# TM4C123GH6PMI.net
KiCad netlist of a schematic drawn in Altium Designer
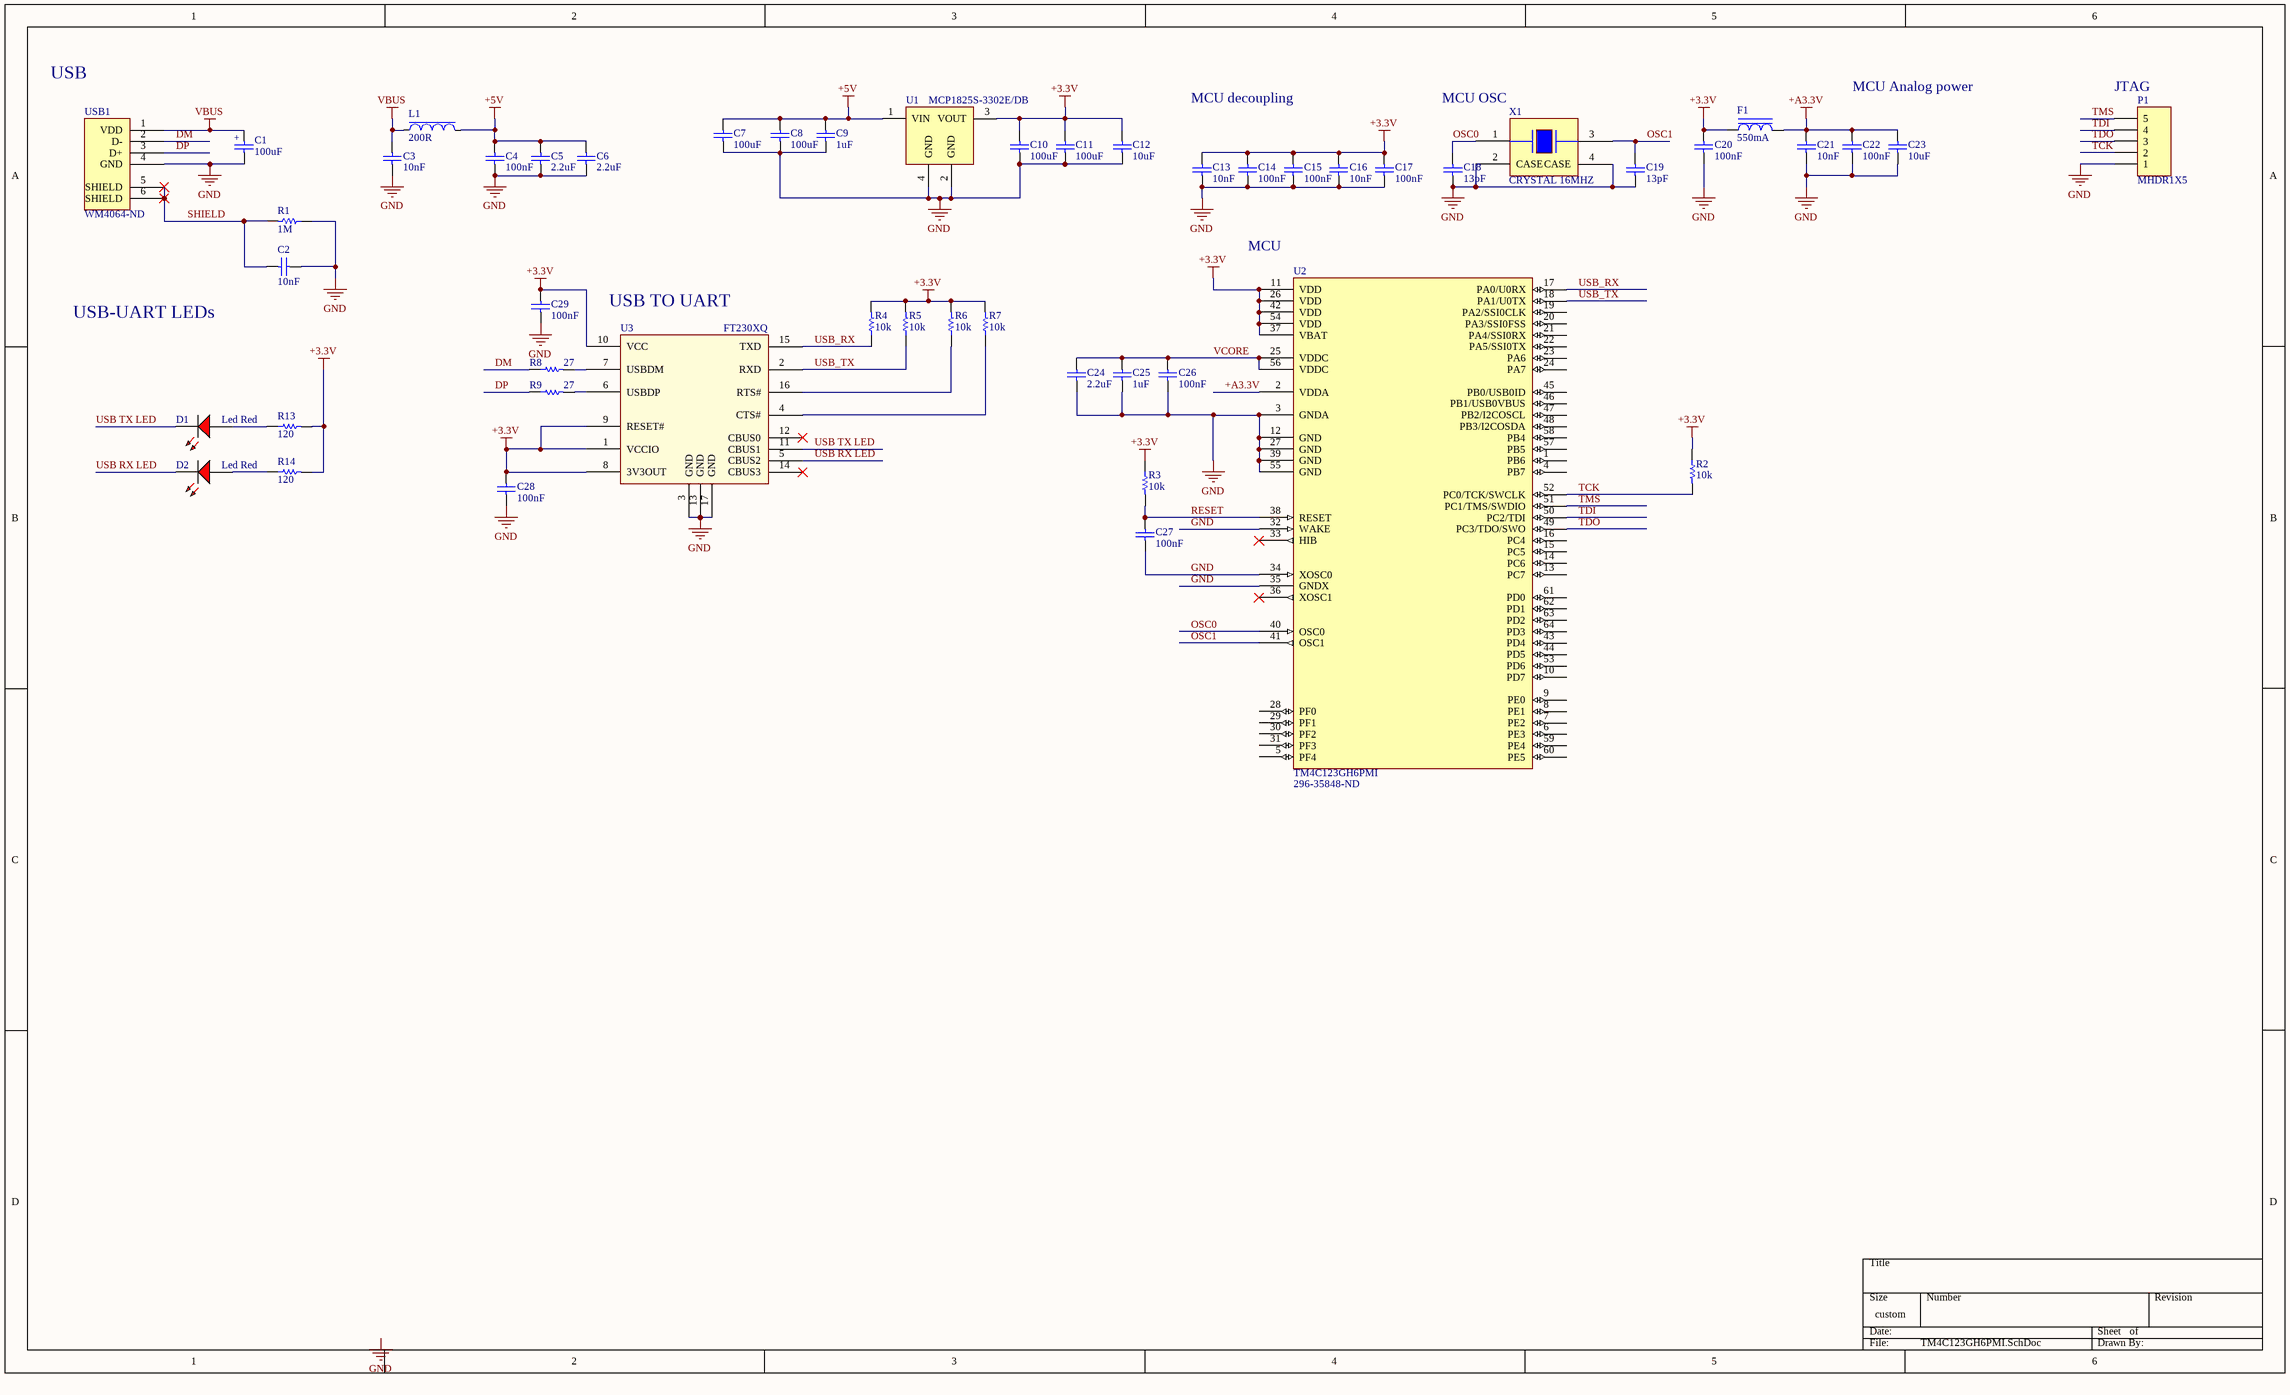
[diagram p0: TM4C123GH6PMI.SchDoc]

(export (version "E")
  (design (tool "Eeschema 10.0.6"))
  (components
    (comp (ref "C1")
      (value "100uF")
      (footprint "CapAlu6.3mmx12.5mm")
      (description "Capacitor 35v 100uF 6.3mm")
      (fields
        (field (name "MANUFACTURER") "Nichicon")
        (field (name "MANUFACTURER PART NUMBER") "UHV1V101MED")
      )
      (libsource (lib "Capacitors") (part "100uF_35v_6.3x12.5"))
    )
    (comp (ref "C2")
      (value "10nF")
      (footprint "CAP_1206")
      (description "CAP CER 10000PF 500V X7R 1206")
      (fields
        (field (name "MANUFACTURER") "Samsung Electro-Mechanics America, Inc")
        (field (name "MANUFACTURER PART NUMBER") "CL31B103KGFNNNE")
      )
      (libsource (lib "Capacitors") (part "10nF_500V_1206"))
    )
    (comp (ref "C3")
      (value "10nF")
      (footprint "CAP_0402_M")
      (description "CAP CER 10000PF 50V 10% X7R 0402")
      (fields
        (field (name "MANUFACTURER") "Kemet")
        (field (name "MANUFACTURER PART NUMBER") "C0402C103K5RACTU")
      )
      (libsource (lib "Capacitors") (part "10nF_50V_0402"))
    )
    (comp (ref "C4")
      (value "100nF")
      (footprint "CAP_0402_M")
      (description "CAP CER 100NF 50V 20% X5R 0402")
      (fields
        (field (name "MANUFACTURER") "TDK Corporation")
        (field (name "MANUFACTURER PART NUMBER") "C1005X5R1H104M050BB")
      )
      (libsource (lib "Capacitors") (part "100nF_50V_0402"))
    )
    (comp (ref "C5")
      (value "2.2uF")
      (footprint "CAP_0402_M")
      (description "CAP CER 2.2UF 10V 20% X5R 0402")
      (fields
        (field (name "MANUFACTURER") "Taiyo Yuden")
        (field (name "MANUFACTURER PART NUMBER") "LMK105BJ225MV-F")
      )
      (libsource (lib "Capacitors") (part "2.2uF_10V_0402"))
    )
    (comp (ref "C6")
      (value "2.2uF")
      (footprint "CAP_0402_M")
      (description "CAP CER 2.2UF 10V 20% X5R 0402")
      (fields
        (field (name "MANUFACTURER") "Taiyo Yuden")
        (field (name "MANUFACTURER PART NUMBER") "LMK105BJ225MV-F")
      )
      (libsource (lib "Capacitors") (part "2.2uF_10V_0402"))
    )
    (comp (ref "C7")
      (value "100uF")
      (footprint "CAP_1206")
      (description "CAP CER 100UF 6.3V X5R 1206")
      (fields
        (field (name "MANUFACTURER") "Murata Electronics North America")
        (field (name "MANUFACTURER PART NUMBER") "GRM31CR60J107ME39L")
      )
      (libsource (lib "Capacitors") (part "100uF_6.3v_1206_X5R"))
    )
    (comp (ref "C8")
      (value "100uF")
      (footprint "CAP_1206")
      (description "CAP CER 100UF 6.3V X5R 1206")
      (fields
        (field (name "MANUFACTURER") "Murata Electronics North America")
        (field (name "MANUFACTURER PART NUMBER") "GRM31CR60J107ME39L")
      )
      (libsource (lib "Capacitors") (part "100uF_6.3v_1206_X5R"))
    )
    (comp (ref "C9")
      (value "1uF")
      (footprint "CAP_0402_M")
      (description "CAP CER 1UF 25V 10% X5R 0402")
      (fields
        (field (name "MANUFACTURER") "TDK Corporation")
        (field (name "MANUFACTURER PART NUMBER") "C1005X5R1E105K050BC")
      )
      (libsource (lib "Capacitors") (part "1uF_25V_0402"))
    )
    (comp (ref "C10")
      (value "100uF")
      (footprint "CAP_1206")
      (description "CAP CER 100UF 6.3V X5R 1206")
      (fields
        (field (name "MANUFACTURER") "Murata Electronics North America")
        (field (name "MANUFACTURER PART NUMBER") "GRM31CR60J107ME39L")
      )
      (libsource (lib "Capacitors") (part "100uF_6.3v_1206_X5R"))
    )
    (comp (ref "C11")
      (value "100uF")
      (footprint "CAP_1206")
      (description "CAP CER 100UF 6.3V X5R 1206")
      (fields
        (field (name "MANUFACTURER") "Murata Electronics North America")
        (field (name "MANUFACTURER PART NUMBER") "GRM31CR60J107ME39L")
      )
      (libsource (lib "Capacitors") (part "100uF_6.3v_1206_X5R"))
    )
    (comp (ref "C12")
      (value "10uF")
      (footprint "CAP_0603")
      (description "CAP CER 10UF 10V 20% X5R 0603")
      (fields
        (field (name "MANUFACTURER") "Taiyo Yuden")
        (field (name "MANUFACTURER PART NUMBER") "LMK107BBJ106MAHT")
      )
      (libsource (lib "Capacitors") (part "10uF_10V_0603"))
    )
    (comp (ref "C13")
      (value "10nF")
      (footprint "CAP_0402_M")
      (description "CAP CER 10000PF 50V 10% X7R 0402")
      (fields
        (field (name "MANUFACTURER") "Kemet")
        (field (name "MANUFACTURER PART NUMBER") "C0402C103K5RACTU")
      )
      (libsource (lib "Capacitors") (part "10nF_50V_0402"))
    )
    (comp (ref "C14")
      (value "100nF")
      (footprint "CAP_0402_M")
      (description "CAP CER 100NF 50V 20% X5R 0402")
      (fields
        (field (name "MANUFACTURER") "TDK Corporation")
        (field (name "MANUFACTURER PART NUMBER") "C1005X5R1H104M050BB")
      )
      (libsource (lib "Capacitors") (part "100nF_50V_0402"))
    )
    (comp (ref "C15")
      (value "100nF")
      (footprint "CAP_0402_M")
      (description "CAP CER 100NF 50V 20% X5R 0402")
      (fields
        (field (name "MANUFACTURER") "TDK Corporation")
        (field (name "MANUFACTURER PART NUMBER") "C1005X5R1H104M050BB")
      )
      (libsource (lib "Capacitors") (part "100nF_50V_0402"))
    )
    (comp (ref "C16")
      (value "10nF")
      (footprint "CAP_0402_M")
      (description "CAP CER 10000PF 50V 10% X7R 0402")
      (fields
        (field (name "MANUFACTURER") "Kemet")
        (field (name "MANUFACTURER PART NUMBER") "C0402C103K5RACTU")
      )
      (libsource (lib "Capacitors") (part "10nF_50V_0402"))
    )
    (comp (ref "C17")
      (value "100nF")
      (footprint "CAP_0402_M")
      (description "CAP CER 100NF 50V 20% X5R 0402")
      (fields
        (field (name "MANUFACTURER") "TDK Corporation")
        (field (name "MANUFACTURER PART NUMBER") "C1005X5R1H104M050BB")
      )
      (libsource (lib "Capacitors") (part "100nF_50V_0402"))
    )
    (comp (ref "C18")
      (value "13pF")
      (footprint "CAP_0402_M")
      (description "CAP CER 13PF 50V 5% NP0 0402")
      (fields
        (field (name "MANUFACTURER") "Samsung Electro-Mechanics America, Inc")
        (field (name "MANUFACTURER PART NUMBER") "CL05C130JB5NNNC")
      )
      (libsource (lib "Capacitors") (part "13pF_50V_0402"))
    )
    (comp (ref "C19")
      (value "13pF")
      (footprint "CAP_0402_M")
      (description "CAP CER 13PF 50V 5% NP0 0402")
      (fields
        (field (name "MANUFACTURER") "Samsung Electro-Mechanics America, Inc")
        (field (name "MANUFACTURER PART NUMBER") "CL05C130JB5NNNC")
      )
      (libsource (lib "Capacitors") (part "13pF_50V_0402"))
    )
    (comp (ref "C20")
      (value "100nF")
      (footprint "CAP_0402_M")
      (description "CAP CER 100NF 50V 20% X5R 0402")
      (fields
        (field (name "MANUFACTURER") "TDK Corporation")
        (field (name "MANUFACTURER PART NUMBER") "C1005X5R1H104M050BB")
      )
      (libsource (lib "Capacitors") (part "100nF_50V_0402"))
    )
    (comp (ref "C21")
      (value "10nF")
      (footprint "CAP_0402_M")
      (description "CAP CER 10000PF 50V 10% X7R 0402")
      (fields
        (field (name "MANUFACTURER") "Kemet")
        (field (name "MANUFACTURER PART NUMBER") "C0402C103K5RACTU")
      )
      (libsource (lib "Capacitors") (part "10nF_50V_0402"))
    )
    (comp (ref "C22")
      (value "100nF")
      (footprint "CAP_0402_M")
      (description "CAP CER 100NF 50V 20% X5R 0402")
      (fields
        (field (name "MANUFACTURER") "TDK Corporation")
        (field (name "MANUFACTURER PART NUMBER") "C1005X5R1H104M050BB")
      )
      (libsource (lib "Capacitors") (part "100nF_50V_0402"))
    )
    (comp (ref "C23")
      (value "10uF")
      (footprint "CAP_0603")
      (description "CAP CER 10UF 10V 20% X5R 0603")
      (fields
        (field (name "MANUFACTURER") "Taiyo Yuden")
        (field (name "MANUFACTURER PART NUMBER") "LMK107BBJ106MAHT")
      )
      (libsource (lib "Capacitors") (part "10uF_10V_0603"))
    )
    (comp (ref "C24")
      (value "2.2uF")
      (footprint "CAP_0603")
      (description "CAP CER 2.2UF 35V 10% X5R 0603")
      (fields
        (field (name "MANUFACTURER") "Murata Electronics North America")
        (field (name "MANUFACTURER PART NUMBER") "GRM188R6YA225KA12D")
      )
      (libsource (lib "Capacitors") (part "2.2uF_35V_0603"))
    )
    (comp (ref "C25")
      (value "1uF")
      (footprint "CAP_0402_M")
      (description "CAP CER 1UF 25V 10% X5R 0402")
      (fields
        (field (name "MANUFACTURER") "TDK Corporation")
        (field (name "MANUFACTURER PART NUMBER") "C1005X5R1E105K050BC")
      )
      (libsource (lib "Capacitors") (part "1uF_25V_0402"))
    )
    (comp (ref "C26")
      (value "100nF")
      (footprint "CAP_0402_M")
      (description "CAP CER 100NF 50V 20% X5R 0402")
      (fields
        (field (name "MANUFACTURER") "TDK Corporation")
        (field (name "MANUFACTURER PART NUMBER") "C1005X5R1H104M050BB")
      )
      (libsource (lib "Capacitors") (part "100nF_50V_0402"))
    )
    (comp (ref "C27")
      (value "100nF")
      (footprint "CAP_0402_M")
      (description "CAP CER 100NF 50V 20% X5R 0402")
      (fields
        (field (name "MANUFACTURER") "TDK Corporation")
        (field (name "MANUFACTURER PART NUMBER") "C1005X5R1H104M050BB")
      )
      (libsource (lib "Capacitors") (part "100nF_50V_0402"))
    )
    (comp (ref "C28")
      (value "100nF")
      (footprint "CAP_0402_M")
      (description "CAP CER 100NF 50V 20% X5R 0402")
      (fields
        (field (name "MANUFACTURER") "TDK Corporation")
        (field (name "MANUFACTURER PART NUMBER") "C1005X5R1H104M050BB")
      )
      (libsource (lib "Capacitors") (part "100nF_50V_0402"))
    )
    (comp (ref "C29")
      (value "100nF")
      (footprint "CAP_0402_M")
      (description "CAP CER 100NF 50V 20% X5R 0402")
      (fields
        (field (name "MANUFACTURER") "TDK Corporation")
        (field (name "MANUFACTURER PART NUMBER") "C1005X5R1H104M050BB")
      )
      (libsource (lib "Capacitors") (part "100nF_50V_0402"))
    )
    (comp (ref "D1")
      (value "Led Red")
      (footprint "TOPLED 0805")
      (description "LED TOPLED 630NM SUP RED CLR SMD")
      (fields
        (field (name "MANUFACTURER") "OSRAM Opto Semiconductors Inc")
        (field (name "MANUFACTURER PART NUMBER") "LS M67K-H2L1-1-Z")
      )
      (libsource (lib "Diodes") (part "TOPLED 0803"))
    )
    (comp (ref "D2")
      (value "Led Red")
      (footprint "TOPLED 0805")
      (description "LED TOPLED 630NM SUP RED CLR SMD")
      (fields
        (field (name "MANUFACTURER") "OSRAM Opto Semiconductors Inc")
        (field (name "MANUFACTURER PART NUMBER") "LS M67K-H2L1-1-Z")
      )
      (libsource (lib "Diodes") (part "TOPLED 0803"))
    )
    (comp (ref "F1")
      (value "550mA")
      (footprint "RES_0402_M")
      (description "FERRITE CHIP 40 OHM 550MA 0402")
      (fields
        (field (name "MANUFACTURER") "TDK Corporation")
        (field (name "MANUFACTURER PART NUMBER") "MMZ1005Y400CT000")
      )
      (libsource (lib "Resistors") (part "40O_550mA_0402"))
    )
    (comp (ref "L1")
      (value "200R")
      (footprint "IND_0603")
      (description "FILTER CHIP 220 OHM 2A 0603")
      (fields
        (field (name "MANUFACTURER") "Murata Electronics North America")
        (field (name "MANUFACTURER PART NUMBER") "BLM18EG221SN1D")
      )
      (libsource (lib "Inductors") (part "Ferrite_200 ohms_2A"))
    )
    (comp (ref "P1")
      (value "MHDR1X5")
      (footprint "MHDR1X5")
      (description "Header, 5-Pin")
      (fields (field (name "PUBLISHER") "Altium Limited"))
      (libsource (lib "Miscellaneous Connectors") (part "MHDR1X5"))
    )
    (comp (ref "R1")
      (value "1M")
      (footprint "RES_1206")
      (description "RES SMD 1M OHM 5% 1/4W 1206")
      (fields
        (field (name "MANUFACTURER") "Panasonic Electronic Components")
        (field (name "MANUFACTURER PART NUMBER") "ERJ-8GEYJ105V")
      )
      (libsource (lib "Resistors") (part "1M_5%_1206"))
    )
    (comp (ref "R2")
      (value "10k")
      (footprint "RES_0402_M")
      (description "RES SMD 10K OHM 1% 1/10W 0402")
      (fields
        (field (name "MANUFACTURER") "Panasonic Electronic Components")
        (field (name "MANUFACTURER PART NUMBER") "ERJ-2RKF1002X")
      )
      (libsource (lib "Resistors") (part "10k_1%_0402"))
    )
    (comp (ref "R3")
      (value "10k")
      (footprint "RES_0402_M")
      (description "RES SMD 10K OHM 1% 1/10W 0402")
      (fields
        (field (name "MANUFACTURER") "Panasonic Electronic Components")
        (field (name "MANUFACTURER PART NUMBER") "ERJ-2RKF1002X")
      )
      (libsource (lib "Resistors") (part "10k_1%_0402"))
    )
    (comp (ref "R4")
      (value "10k")
      (footprint "RES_0402_M")
      (description "RES SMD 10K OHM 1% 1/10W 0402")
      (fields
        (field (name "MANUFACTURER") "Panasonic Electronic Components")
        (field (name "MANUFACTURER PART NUMBER") "ERJ-2RKF1002X")
      )
      (libsource (lib "Resistors") (part "10k_1%_0402"))
    )
    (comp (ref "R5")
      (value "10k")
      (footprint "RES_0402_M")
      (description "RES SMD 10K OHM 1% 1/10W 0402")
      (fields
        (field (name "MANUFACTURER") "Panasonic Electronic Components")
        (field (name "MANUFACTURER PART NUMBER") "ERJ-2RKF1002X")
      )
      (libsource (lib "Resistors") (part "10k_1%_0402"))
    )
    (comp (ref "R6")
      (value "10k")
      (footprint "RES_0402_M")
      (description "RES SMD 10K OHM 1% 1/10W 0402")
      (fields
        (field (name "MANUFACTURER") "Panasonic Electronic Components")
        (field (name "MANUFACTURER PART NUMBER") "ERJ-2RKF1002X")
      )
      (libsource (lib "Resistors") (part "10k_1%_0402"))
    )
    (comp (ref "R7")
      (value "10k")
      (footprint "RES_0402_M")
      (description "RES SMD 10K OHM 1% 1/10W 0402")
      (fields
        (field (name "MANUFACTURER") "Panasonic Electronic Components")
        (field (name "MANUFACTURER PART NUMBER") "ERJ-2RKF1002X")
      )
      (libsource (lib "Resistors") (part "10k_1%_0402"))
    )
    (comp (ref "R8")
      (value "27")
      (footprint "RES_0402_M")
      (description "RES SMD 27 OHM 1% 1/10W 0402")
      (fields
        (field (name "MANUFACTURER") "Panasonic Electronic Components")
        (field (name "MANUFACTURER PART NUMBER") "ERJ-2RKF27R0X")
      )
      (libsource (lib "Resistors") (part "27_1%_0402"))
    )
    (comp (ref "R9")
      (value "27")
      (footprint "RES_0402_M")
      (description "RES SMD 27 OHM 1% 1/10W 0402")
      (fields
        (field (name "MANUFACTURER") "Panasonic Electronic Components")
        (field (name "MANUFACTURER PART NUMBER") "ERJ-2RKF27R0X")
      )
      (libsource (lib "Resistors") (part "27_1%_0402"))
    )
    (comp (ref "R13")
      (value "120")
      (footprint "RES_0402_M")
      (description "RES SMD 120 OHM 1% 1/10W 0402")
      (fields
        (field (name "MANUFACTURER") "Panasonic Electronic Components")
        (field (name "MANUFACTURER PART NUMBER") "ERJ-2RKF1200X")
      )
      (libsource (lib "Resistors") (part "120_1%_0402"))
    )
    (comp (ref "R14")
      (value "120")
      (footprint "RES_0402_M")
      (description "RES SMD 120 OHM 1% 1/10W 0402")
      (fields
        (field (name "MANUFACTURER") "Panasonic Electronic Components")
        (field (name "MANUFACTURER PART NUMBER") "ERJ-2RKF1200X")
      )
      (libsource (lib "Resistors") (part "120_1%_0402"))
    )
    (comp (ref "U1")
      (value "MCP1825S-3302E/DB")
      (footprint "SOT230P700X180-4N")
      (description "500 mA, Low Voltage, Low Quiescent Current LDO Regulator")
      (fields (field (name "MANUFACTURER") "Microchip Technology"))
      (libsource (lib "ICs") (part "MCP1825S-3302E/DB"))
    )
    (comp (ref "U2")
      (value "TM4C123GH6PMI")
      (footprint "TSQFP50P1200X1200X120-64N")
      (description "Tiva TM4C123GH6PM Microcontroller ARM Cortex 80 MHz FPU")
      (fields (field (name "SUPPLIER PART NUMBER 1") "296-35848-ND"))
      (libsource (lib "ICs") (part "TM4C123GH6PMI"))
    )
    (comp (ref "U3")
      (value "FT230XQ")
      (footprint "QFN65P400X400X80_HS-17N")
      (description "IC USB SERIAL BASIC UART 16QFN")
      (fields
        (field (name "MANUFACTURER") "FTDI, Future Technology Devices International Ltd")
        (field (name "MANUFACTURER PART NUMBER") "FT230XQ-R")
      )
      (libsource (lib "ICs") (part "FT230XQ-R"))
    )
    (comp (ref "USB1")
      (value "USB type-B jack")
      (footprint "USB2.5-2H4E")
      (fields (field (name "SUPPLIER PART NUMBER 1") "WM4064-ND"))
      (libsource (lib "Connectors") (part "MOLEX 0670688010"))
    )
    (comp (ref "X1")
      (value "CRYSTAL 16MHZ")
      (footprint "CRYSTAL_3.2x2.5")
      (description "CRYSTAL 16MHZ 20PF SMD")
      (fields
        (field (name "MANUFACTURER") "CTS-Frequency Controls")
        (field (name "MANUFACTURER PART NUMBER") "403C35E16M00000")
      )
      (libsource (lib "ICs") (part "403C35E16M00000"))
    )
  )
  (nets
    (net (code "1") (name "+3.3V") (class "Default")
      (node (ref "C10") (pin "1") (pinfunction "1_1") (pintype "passive"))
      (node (ref "C11") (pin "1") (pinfunction "1_1") (pintype "passive"))
      (node (ref "C12") (pin "1") (pinfunction "1_1") (pintype "passive"))
      (node (ref "C13") (pin "2") (pinfunction "2_2") (pintype "passive"))
      (node (ref "C14") (pin "2") (pinfunction "2_2") (pintype "passive"))
      (node (ref "C15") (pin "2") (pinfunction "2_2") (pintype "passive"))
      (node (ref "C16") (pin "2") (pinfunction "2_2") (pintype "passive"))
      (node (ref "C17") (pin "2") (pinfunction "2_2") (pintype "passive"))
      (node (ref "C20") (pin "2") (pinfunction "2_2") (pintype "passive"))
      (node (ref "C28") (pin "2") (pinfunction "2_2") (pintype "passive"))
      (node (ref "C29") (pin "2") (pinfunction "2_2") (pintype "passive"))
      (node (ref "F1") (pin "1") (pinfunction "1_1") (pintype "passive"))
      (node (ref "R13") (pin "2") (pinfunction "2_2") (pintype "passive"))
      (node (ref "R14") (pin "2") (pinfunction "2_2") (pintype "passive"))
      (node (ref "R2") (pin "1") (pinfunction "1_1") (pintype "passive"))
      (node (ref "R3") (pin "1") (pinfunction "1_1") (pintype "passive"))
      (node (ref "R4") (pin "2") (pinfunction "2_2") (pintype "passive"))
      (node (ref "R5") (pin "2") (pinfunction "2_2") (pintype "passive"))
      (node (ref "R6") (pin "2") (pinfunction "2_2") (pintype "passive"))
      (node (ref "R7") (pin "2") (pinfunction "2_2") (pintype "passive"))
      (node (ref "U1") (pin "3") (pinfunction "VOUT_3") (pintype "power_in"))
      (node (ref "U2") (pin "11") (pinfunction "VDD_11") (pintype "power_in"))
      (node (ref "U2") (pin "26") (pinfunction "VDD_26") (pintype "power_in"))
      (node (ref "U2") (pin "37") (pinfunction "VBAT_37") (pintype "power_in"))
      (node (ref "U2") (pin "42") (pinfunction "VDD_42") (pintype "power_in"))
      (node (ref "U2") (pin "54") (pinfunction "VDD_54") (pintype "power_in"))
      (node (ref "U3") (pin "1") (pinfunction "VCCIO_1") (pintype "passive"))
      (node (ref "U3") (pin "10") (pinfunction "VCC_10") (pintype "passive"))
      (node (ref "U3") (pin "8") (pinfunction "3V3OUT_8") (pintype "passive"))
      (node (ref "U3") (pin "9") (pinfunction "RESET#_9") (pintype "passive"))
    )
    (net (code "2") (name "+5V") (class "Default")
      (node (ref "C4") (pin "2") (pinfunction "2_2") (pintype "passive"))
      (node (ref "C5") (pin "2") (pinfunction "2_2") (pintype "passive"))
      (node (ref "C6") (pin "2") (pinfunction "2_2") (pintype "passive"))
      (node (ref "C7") (pin "1") (pinfunction "1_1") (pintype "passive"))
      (node (ref "C8") (pin "1") (pinfunction "1_1") (pintype "passive"))
      (node (ref "C9") (pin "2") (pinfunction "2_2") (pintype "passive"))
      (node (ref "L1") (pin "2") (pinfunction "2_2") (pintype "passive"))
      (node (ref "U1") (pin "1") (pinfunction "VIN_1") (pintype "power_in"))
    )
    (net (code "3") (name "+A3.3V") (class "Default")
      (node (ref "C21") (pin "2") (pinfunction "2_2") (pintype "passive"))
      (node (ref "C22") (pin "2") (pinfunction "2_2") (pintype "passive"))
      (node (ref "C23") (pin "2") (pinfunction "2_2") (pintype "passive"))
      (node (ref "F1") (pin "2") (pinfunction "2_2") (pintype "passive"))
      (node (ref "U2") (pin "2") (pinfunction "VDDA_2") (pintype "power_in"))
    )
    (net (code "4") (name "/DM") (class "Default")
      (node (ref "R8") (pin "1") (pinfunction "1_1") (pintype "passive"))
      (node (ref "USB1") (pin "2") (pinfunction "D-_2") (pintype "passive"))
    )
    (net (code "5") (name "/DP") (class "Default")
      (node (ref "R9") (pin "1") (pinfunction "1_1") (pintype "passive"))
      (node (ref "USB1") (pin "3") (pinfunction "D+_3") (pintype "passive"))
    )
    (net (code "6") (name "/OSC0") (class "Default")
      (node (ref "C18") (pin "2") (pinfunction "2_2") (pintype "passive"))
      (node (ref "U2") (pin "40") (pinfunction "OSC0_40") (pintype "input"))
      (node (ref "X1") (pin "1") (pintype "passive"))
    )
    (net (code "7") (name "/OSC1") (class "Default")
      (node (ref "C19") (pin "2") (pinfunction "2_2") (pintype "passive"))
      (node (ref "U2") (pin "41") (pinfunction "OSC1_41") (pintype "output"))
      (node (ref "X1") (pin "3") (pintype "passive"))
    )
    (net (code "8") (name "/RESET") (class "Default")
      (node (ref "C27") (pin "2") (pinfunction "2_2") (pintype "passive"))
      (node (ref "R3") (pin "2") (pinfunction "2_2") (pintype "passive"))
      (node (ref "U2") (pin "38") (pinfunction "RESET_38") (pintype "input"))
    )
    (net (code "9") (name "/SHIELD") (class "Default")
      (node (ref "C2") (pin "2") (pinfunction "2_2") (pintype "passive"))
      (node (ref "R1") (pin "2") (pinfunction "2_2") (pintype "passive"))
      (node (ref "USB1") (pin "5") (pinfunction "SHIELD_5") (pintype "passive"))
      (node (ref "USB1") (pin "6") (pinfunction "SHIELD_6") (pintype "passive"))
    )
    (net (code "10") (name "/TCK") (class "Default")
      (node (ref "P1") (pin "2") (pinfunction "2_2") (pintype "passive"))
      (node (ref "R2") (pin "2") (pinfunction "2_2") (pintype "passive"))
      (node (ref "U2") (pin "52") (pinfunction "PC0/TCK/SWCLK_52") (pintype "bidirectional"))
    )
    (net (code "11") (name "/TDI") (class "Default")
      (node (ref "P1") (pin "4") (pinfunction "4_4") (pintype "passive"))
      (node (ref "U2") (pin "50") (pinfunction "PC2/TDI_50") (pintype "bidirectional"))
    )
    (net (code "12") (name "/TDO") (class "Default")
      (node (ref "P1") (pin "3") (pinfunction "3_3") (pintype "passive"))
      (node (ref "U2") (pin "49") (pinfunction "PC3/TDO/SWO_49") (pintype "bidirectional"))
    )
    (net (code "13") (name "/TMS") (class "Default")
      (node (ref "P1") (pin "5") (pinfunction "5_5") (pintype "passive"))
      (node (ref "U2") (pin "51") (pinfunction "PC1/TMS/SWDIO_51") (pintype "bidirectional"))
    )
    (net (code "14") (name "/USB RX LED") (class "Default")
      (node (ref "D2") (pin "2") (pinfunction "K_2") (pintype "passive"))
      (node (ref "U3") (pin "5") (pinfunction "CBUS2_5") (pintype "passive"))
    )
    (net (code "15") (name "/USB TX LED") (class "Default")
      (node (ref "D1") (pin "2") (pinfunction "K_2") (pintype "passive"))
      (node (ref "U3") (pin "11") (pinfunction "CBUS1_11") (pintype "passive"))
    )
    (net (code "16") (name "/USB_RX") (class "Default")
      (node (ref "R4") (pin "1") (pinfunction "1_1") (pintype "passive"))
      (node (ref "U2") (pin "17") (pinfunction "PA0/U0RX_17") (pintype "bidirectional"))
      (node (ref "U3") (pin "15") (pinfunction "TXD_15") (pintype "passive"))
    )
    (net (code "17") (name "/USB_TX") (class "Default")
      (node (ref "R5") (pin "1") (pinfunction "1_1") (pintype "passive"))
      (node (ref "U2") (pin "18") (pinfunction "PA1/U0TX_18") (pintype "bidirectional"))
      (node (ref "U3") (pin "2") (pinfunction "RXD_2") (pintype "passive"))
    )
    (net (code "18") (name "/VCORE") (class "Default")
      (node (ref "C24") (pin "2") (pinfunction "2_2") (pintype "passive"))
      (node (ref "C25") (pin "2") (pinfunction "2_2") (pintype "passive"))
      (node (ref "C26") (pin "2") (pinfunction "2_2") (pintype "passive"))
      (node (ref "U2") (pin "25") (pinfunction "VDDC_25") (pintype "power_in"))
      (node (ref "U2") (pin "56") (pinfunction "VDDC_56") (pintype "power_in"))
    )
    (net (code "19") (name "GND") (class "Default")
      (node (ref "C1") (pin "2") (pinfunction "2_2") (pintype "passive"))
      (node (ref "C10") (pin "2") (pinfunction "2_2") (pintype "passive"))
      (node (ref "C11") (pin "2") (pinfunction "2_2") (pintype "passive"))
      (node (ref "C12") (pin "2") (pinfunction "2_2") (pintype "passive"))
      (node (ref "C13") (pin "1") (pinfunction "1_1") (pintype "passive"))
      (node (ref "C14") (pin "1") (pinfunction "1_1") (pintype "passive"))
      (node (ref "C15") (pin "1") (pinfunction "1_1") (pintype "passive"))
      (node (ref "C16") (pin "1") (pinfunction "1_1") (pintype "passive"))
      (node (ref "C17") (pin "1") (pinfunction "1_1") (pintype "passive"))
      (node (ref "C18") (pin "1") (pinfunction "1_1") (pintype "passive"))
      (node (ref "C19") (pin "1") (pinfunction "1_1") (pintype "passive"))
      (node (ref "C2") (pin "1") (pinfunction "1_1") (pintype "passive"))
      (node (ref "C20") (pin "1") (pinfunction "1_1") (pintype "passive"))
      (node (ref "C21") (pin "1") (pinfunction "1_1") (pintype "passive"))
      (node (ref "C22") (pin "1") (pinfunction "1_1") (pintype "passive"))
      (node (ref "C23") (pin "1") (pinfunction "1_1") (pintype "passive"))
      (node (ref "C24") (pin "1") (pinfunction "1_1") (pintype "passive"))
      (node (ref "C25") (pin "1") (pinfunction "1_1") (pintype "passive"))
      (node (ref "C26") (pin "1") (pinfunction "1_1") (pintype "passive"))
      (node (ref "C27") (pin "1") (pinfunction "1_1") (pintype "passive"))
      (node (ref "C28") (pin "1") (pinfunction "1_1") (pintype "passive"))
      (node (ref "C29") (pin "1") (pinfunction "1_1") (pintype "passive"))
      (node (ref "C3") (pin "1") (pinfunction "1_1") (pintype "passive"))
      (node (ref "C4") (pin "1") (pinfunction "1_1") (pintype "passive"))
      (node (ref "C5") (pin "1") (pinfunction "1_1") (pintype "passive"))
      (node (ref "C6") (pin "1") (pinfunction "1_1") (pintype "passive"))
      (node (ref "C7") (pin "2") (pinfunction "2_2") (pintype "passive"))
      (node (ref "C8") (pin "2") (pinfunction "2_2") (pintype "passive"))
      (node (ref "C9") (pin "1") (pinfunction "1_1") (pintype "passive"))
      (node (ref "P1") (pin "1") (pinfunction "1_1") (pintype "passive"))
      (node (ref "R1") (pin "1") (pinfunction "1_1") (pintype "passive"))
      (node (ref "U1") (pin "2") (pinfunction "GND_2") (pintype "power_in"))
      (node (ref "U1") (pin "4") (pinfunction "GND_4") (pintype "power_in"))
      (node (ref "U2") (pin "12") (pinfunction "GND_12") (pintype "power_in"))
      (node (ref "U2") (pin "27") (pinfunction "GND_27") (pintype "power_in"))
      (node (ref "U2") (pin "3") (pinfunction "GNDA_3") (pintype "power_in"))
      (node (ref "U2") (pin "32") (pinfunction "WAKE_32") (pintype "input"))
      (node (ref "U2") (pin "34") (pinfunction "XOSC0_34") (pintype "input"))
      (node (ref "U2") (pin "35") (pinfunction "GNDX_35") (pintype "power_in"))
      (node (ref "U2") (pin "39") (pinfunction "GND_39") (pintype "power_in"))
      (node (ref "U2") (pin "55") (pinfunction "GND_55") (pintype "power_in"))
      (node (ref "U3") (pin "13") (pinfunction "GND_13") (pintype "passive"))
      (node (ref "U3") (pin "17") (pinfunction "GND_17") (pintype "passive"))
      (node (ref "U3") (pin "3") (pinfunction "GND_3") (pintype "passive"))
      (node (ref "USB1") (pin "4") (pinfunction "GND_4") (pintype "power_in"))
      (node (ref "X1") (pin "2") (pinfunction "CASE_2") (pintype "passive"))
      (node (ref "X1") (pin "4") (pinfunction "CASE_4") (pintype "passive"))
    )
    (net (code "20") (name "Net-(D1-A)") (class "Default")
      (node (ref "D1") (pin "1") (pinfunction "A_1") (pintype "passive"))
      (node (ref "R13") (pin "1") (pinfunction "1_1") (pintype "passive"))
    )
    (net (code "21") (name "Net-(D2-A)") (class "Default")
      (node (ref "D2") (pin "1") (pinfunction "A_1") (pintype "passive"))
      (node (ref "R14") (pin "1") (pinfunction "1_1") (pintype "passive"))
    )
    (net (code "22") (name "Net-(U3-CTS#)") (class "Default")
      (node (ref "R7") (pin "1") (pinfunction "1_1") (pintype "passive"))
      (node (ref "U3") (pin "4") (pinfunction "CTS#_4") (pintype "passive"))
    )
    (net (code "23") (name "Net-(U3-RTS#)") (class "Default")
      (node (ref "R6") (pin "1") (pinfunction "1_1") (pintype "passive"))
      (node (ref "U3") (pin "16") (pinfunction "RTS#_16") (pintype "passive"))
    )
    (net (code "24") (name "Net-(U3-USBDM)") (class "Default")
      (node (ref "R8") (pin "2") (pinfunction "2_2") (pintype "passive"))
      (node (ref "U3") (pin "7") (pinfunction "USBDM_7") (pintype "passive"))
    )
    (net (code "25") (name "Net-(U3-USBDP)") (class "Default")
      (node (ref "R9") (pin "2") (pinfunction "2_2") (pintype "passive"))
      (node (ref "U3") (pin "6") (pinfunction "USBDP_6") (pintype "passive"))
    )
    (net (code "26") (name "VBUS") (class "Default")
      (node (ref "C1") (pin "1") (pinfunction "1_1") (pintype "passive"))
      (node (ref "C3") (pin "2") (pinfunction "2_2") (pintype "passive"))
      (node (ref "L1") (pin "1") (pinfunction "1_1") (pintype "passive"))
      (node (ref "USB1") (pin "1") (pinfunction "VDD_1") (pintype "power_in"))
    )
    (net (code "27") (name "unconnected-(U2-HIB-Pad33)") (class "Default")
      (node (ref "U2") (pin "33") (pinfunction "HIB_33") (pintype "output+no_connect"))
    )
    (net (code "28") (name "unconnected-(U2-PA2{slash}SSI0CLK-Pad19)") (class "Default")
      (node (ref "U2") (pin "19") (pinfunction "PA2/SSI0CLK_19") (pintype "bidirectional"))
    )
    (net (code "29") (name "unconnected-(U2-PA3{slash}SSI0FSS-Pad20)") (class "Default")
      (node (ref "U2") (pin "20") (pinfunction "PA3/SSI0FSS_20") (pintype "bidirectional"))
    )
    (net (code "30") (name "unconnected-(U2-PA4{slash}SSI0RX-Pad21)") (class "Default")
      (node (ref "U2") (pin "21") (pinfunction "PA4/SSI0RX_21") (pintype "bidirectional"))
    )
    (net (code "31") (name "unconnected-(U2-PA5{slash}SSI0TX-Pad22)") (class "Default")
      (node (ref "U2") (pin "22") (pinfunction "PA5/SSI0TX_22") (pintype "bidirectional"))
    )
    (net (code "32") (name "unconnected-(U2-PA6-Pad23)") (class "Default")
      (node (ref "U2") (pin "23") (pinfunction "PA6_23") (pintype "bidirectional"))
    )
    (net (code "33") (name "unconnected-(U2-PA7-Pad24)") (class "Default")
      (node (ref "U2") (pin "24") (pinfunction "PA7_24") (pintype "bidirectional"))
    )
    (net (code "34") (name "unconnected-(U2-PB0{slash}USB0ID-Pad45)") (class "Default")
      (node (ref "U2") (pin "45") (pinfunction "PB0/USB0ID_45") (pintype "bidirectional"))
    )
    (net (code "35") (name "unconnected-(U2-PB1{slash}USB0VBUS-Pad46)") (class "Default")
      (node (ref "U2") (pin "46") (pinfunction "PB1/USB0VBUS_46") (pintype "bidirectional"))
    )
    (net (code "36") (name "unconnected-(U2-PB2{slash}I2COSCL-Pad47)") (class "Default")
      (node (ref "U2") (pin "47") (pinfunction "PB2/I2COSCL_47") (pintype "bidirectional"))
    )
    (net (code "37") (name "unconnected-(U2-PB3{slash}I2COSDA-Pad48)") (class "Default")
      (node (ref "U2") (pin "48") (pinfunction "PB3/I2COSDA_48") (pintype "bidirectional"))
    )
    (net (code "38") (name "unconnected-(U2-PB4-Pad58)") (class "Default")
      (node (ref "U2") (pin "58") (pinfunction "PB4_58") (pintype "bidirectional"))
    )
    (net (code "39") (name "unconnected-(U2-PB5-Pad57)") (class "Default")
      (node (ref "U2") (pin "57") (pinfunction "PB5_57") (pintype "bidirectional"))
    )
    (net (code "40") (name "unconnected-(U2-PB6-Pad1)") (class "Default")
      (node (ref "U2") (pin "1") (pinfunction "PB6_1") (pintype "bidirectional"))
    )
    (net (code "41") (name "unconnected-(U2-PB7-Pad4)") (class "Default")
      (node (ref "U2") (pin "4") (pinfunction "PB7_4") (pintype "bidirectional"))
    )
    (net (code "42") (name "unconnected-(U2-PC4-Pad16)") (class "Default")
      (node (ref "U2") (pin "16") (pinfunction "PC4_16") (pintype "bidirectional"))
    )
    (net (code "43") (name "unconnected-(U2-PC5-Pad15)") (class "Default")
      (node (ref "U2") (pin "15") (pinfunction "PC5_15") (pintype "bidirectional"))
    )
    (net (code "44") (name "unconnected-(U2-PC6-Pad14)") (class "Default")
      (node (ref "U2") (pin "14") (pinfunction "PC6_14") (pintype "bidirectional"))
    )
    (net (code "45") (name "unconnected-(U2-PC7-Pad13)") (class "Default")
      (node (ref "U2") (pin "13") (pinfunction "PC7_13") (pintype "bidirectional"))
    )
    (net (code "46") (name "unconnected-(U2-PD0-Pad61)") (class "Default")
      (node (ref "U2") (pin "61") (pinfunction "PD0_61") (pintype "bidirectional"))
    )
    (net (code "47") (name "unconnected-(U2-PD1-Pad62)") (class "Default")
      (node (ref "U2") (pin "62") (pinfunction "PD1_62") (pintype "bidirectional"))
    )
    (net (code "48") (name "unconnected-(U2-PD2-Pad63)") (class "Default")
      (node (ref "U2") (pin "63") (pinfunction "PD2_63") (pintype "bidirectional"))
    )
    (net (code "49") (name "unconnected-(U2-PD3-Pad64)") (class "Default")
      (node (ref "U2") (pin "64") (pinfunction "PD3_64") (pintype "bidirectional"))
    )
    (net (code "50") (name "unconnected-(U2-PD4-Pad43)") (class "Default")
      (node (ref "U2") (pin "43") (pinfunction "PD4_43") (pintype "bidirectional"))
    )
    (net (code "51") (name "unconnected-(U2-PD5-Pad44)") (class "Default")
      (node (ref "U2") (pin "44") (pinfunction "PD5_44") (pintype "bidirectional"))
    )
    (net (code "52") (name "unconnected-(U2-PD6-Pad53)") (class "Default")
      (node (ref "U2") (pin "53") (pinfunction "PD6_53") (pintype "bidirectional"))
    )
    (net (code "53") (name "unconnected-(U2-PD7-Pad10)") (class "Default")
      (node (ref "U2") (pin "10") (pinfunction "PD7_10") (pintype "bidirectional"))
    )
    (net (code "54") (name "unconnected-(U2-PE0-Pad9)") (class "Default")
      (node (ref "U2") (pin "9") (pinfunction "PE0_9") (pintype "bidirectional"))
    )
    (net (code "55") (name "unconnected-(U2-PE1-Pad8)") (class "Default")
      (node (ref "U2") (pin "8") (pinfunction "PE1_8") (pintype "bidirectional"))
    )
    (net (code "56") (name "unconnected-(U2-PE2-Pad7)") (class "Default")
      (node (ref "U2") (pin "7") (pinfunction "PE2_7") (pintype "bidirectional"))
    )
    (net (code "57") (name "unconnected-(U2-PE3-Pad6)") (class "Default")
      (node (ref "U2") (pin "6") (pinfunction "PE3_6") (pintype "bidirectional"))
    )
    (net (code "58") (name "unconnected-(U2-PE4-Pad59)") (class "Default")
      (node (ref "U2") (pin "59") (pinfunction "PE4_59") (pintype "bidirectional"))
    )
    (net (code "59") (name "unconnected-(U2-PE5-Pad60)") (class "Default")
      (node (ref "U2") (pin "60") (pinfunction "PE5_60") (pintype "bidirectional"))
    )
    (net (code "60") (name "unconnected-(U2-PF0-Pad28)") (class "Default")
      (node (ref "U2") (pin "28") (pinfunction "PF0_28") (pintype "bidirectional"))
    )
    (net (code "61") (name "unconnected-(U2-PF1-Pad29)") (class "Default")
      (node (ref "U2") (pin "29") (pinfunction "PF1_29") (pintype "bidirectional"))
    )
    (net (code "62") (name "unconnected-(U2-PF2-Pad30)") (class "Default")
      (node (ref "U2") (pin "30") (pinfunction "PF2_30") (pintype "bidirectional"))
    )
    (net (code "63") (name "unconnected-(U2-PF3-Pad31)") (class "Default")
      (node (ref "U2") (pin "31") (pinfunction "PF3_31") (pintype "bidirectional"))
    )
    (net (code "64") (name "unconnected-(U2-PF4-Pad5)") (class "Default")
      (node (ref "U2") (pin "5") (pinfunction "PF4_5") (pintype "bidirectional"))
    )
    (net (code "65") (name "unconnected-(U2-XOSC1-Pad36)") (class "Default")
      (node (ref "U2") (pin "36") (pinfunction "XOSC1_36") (pintype "output+no_connect"))
    )
    (net (code "66") (name "unconnected-(U3-CBUS0-Pad12)") (class "Default")
      (node (ref "U3") (pin "12") (pinfunction "CBUS0_12") (pintype "passive+no_connect"))
    )
    (net (code "67") (name "unconnected-(U3-CBUS3-Pad14)") (class "Default")
      (node (ref "U3") (pin "14") (pinfunction "CBUS3_14") (pintype "passive+no_connect"))
    )
  )
)
